# Zoetrope.net
KiCad netlist of a schematic drawn in EAGLE
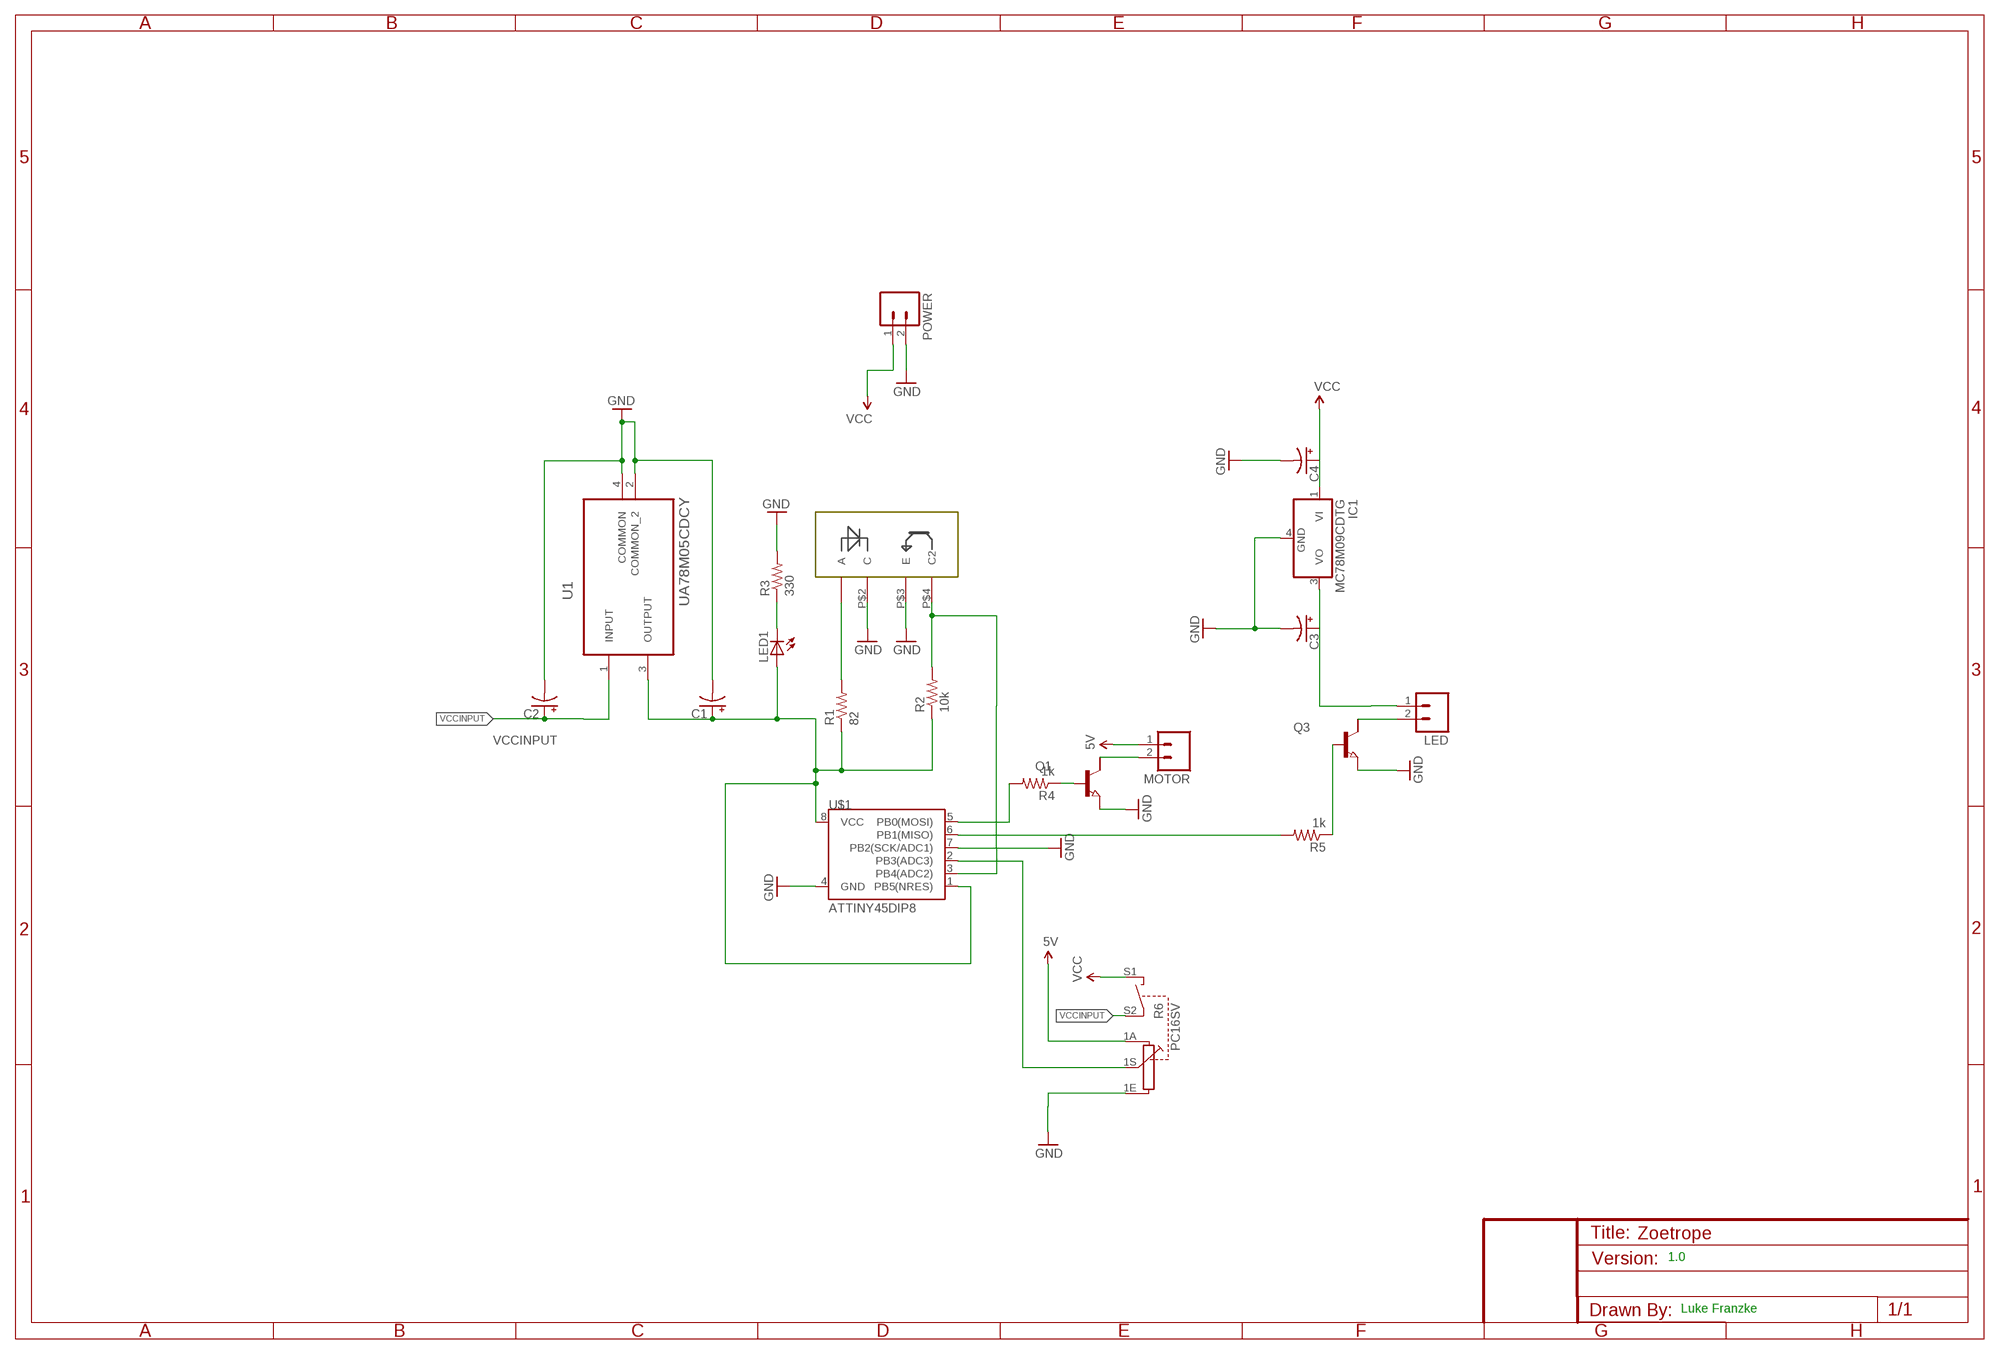
[diagram p0: schematic, sheet 1]

(export (version "E")
  (design (tool "Eeschema 10.0.6"))
  (components
    (comp (ref "C1")
      (value "CAP_POL1206")
      (footprint "eagle-import:EIA3216")
      (libsource (lib "eagle-import") (part "CAP_POL1206"))
    )
    (comp (ref "C2")
      (value "CAP_POL1206")
      (footprint "eagle-import:EIA3216")
      (libsource (lib "eagle-import") (part "CAP_POL1206"))
    )
    (comp (ref "C3")
      (value "CAP_POL1206")
      (footprint "eagle-import:EIA3216")
      (libsource (lib "eagle-import") (part "CAP_POL1206"))
    )
    (comp (ref "C4")
      (value "CAP_POL1206")
      (footprint "eagle-import:EIA3216")
      (libsource (lib "eagle-import") (part "CAP_POL1206"))
    )
    (comp (ref "IC1")
      (value "MC78M09CDTG")
      (footprint "eagle-import:DPACK_3")
      (libsource (lib "eagle-import") (part "MC78M09CDTG"))
    )
    (comp (ref "LED")
      (value "M02")
      (footprint "eagle-import:02P")
      (libsource (lib "eagle-import") (part "M02"))
    )
    (comp (ref "LED1")
      (value "LED1206")
      (footprint "eagle-import:LED-1206")
      (libsource (lib "eagle-import") (part "LED1206"))
    )
    (comp (ref "MOTOR")
      (value "M02")
      (footprint "eagle-import:02P")
      (libsource (lib "eagle-import") (part "M02"))
    )
    (comp (ref "POWER")
      (value "M02")
      (footprint "eagle-import:02P")
      (libsource (lib "eagle-import") (part "M02"))
    )
    (comp (ref "Q1")
      (value "NPN-TRANSISTIOR-2COLSOT89")
      (footprint "eagle-import:SOT89")
      (libsource (lib "eagle-import") (part "NPN-TRANSISTIOR-2COLSOT89"))
    )
    (comp (ref "Q3")
      (value "NPN-TRANSISTIOR-2COLSOT89")
      (footprint "eagle-import:SOT89")
      (libsource (lib "eagle-import") (part "NPN-TRANSISTIOR-2COLSOT89"))
    )
    (comp (ref "R1")
      (value "82")
      (footprint "eagle-import:1206")
      (libsource (lib "eagle-import") (part "RESISTOR1206"))
    )
    (comp (ref "R2")
      (value "10k")
      (footprint "eagle-import:1206")
      (libsource (lib "eagle-import") (part "RESISTOR1206"))
    )
    (comp (ref "R3")
      (value "330")
      (footprint "eagle-import:1206")
      (libsource (lib "eagle-import") (part "RESISTOR1206"))
    )
    (comp (ref "R4")
      (value "1k")
      (footprint "eagle-import:1206")
      (libsource (lib "eagle-import") (part "RESISTOR1206"))
    )
    (comp (ref "R5")
      (value "1k")
      (footprint "eagle-import:1206")
      (libsource (lib "eagle-import") (part "RESISTOR1206"))
    )
    (comp (ref "R6")
      (value "PC16SV")
      (footprint "eagle-import:PC16SV")
      (libsource (lib "eagle-import") (part "PC16SV"))
    )
    (comp (ref "U$1")
      (value "ATTINY45DIP8")
      (footprint "eagle-import:DIP08")
      (libsource (lib "eagle-import") (part "ATTINY45DIP8"))
    )
    (comp (ref "U$2")
      (value "TCRT1000")
      (footprint "eagle-import:TCRT1000")
      (libsource (lib "eagle-import") (part "TCRT1000"))
    )
    (comp (ref "U1")
      (value "UA78M05CDCY")
      (footprint "eagle-import:SOT230P700X180-4N")
      (libsource (lib "eagle-import") (part "UA78M05CDCY"))
    )
  )
  (nets
    (net (code "1") (name "5V") (class "Default")
      (node (ref "C1") (pin "A") (pinfunction "+_A") (pintype "passive"))
      (node (ref "LED1") (pin "A") (pinfunction "A_A") (pintype "passive"))
      (node (ref "MOTOR") (pin "1") (pinfunction "1_1") (pintype "passive"))
      (node (ref "R1") (pin "1") (pinfunction "1_1") (pintype "passive"))
      (node (ref "R2") (pin "1") (pinfunction "1_1") (pintype "passive"))
      (node (ref "R6") (pin "1A") (pinfunction "1A_1A") (pintype "passive"))
      (node (ref "U$1") (pin "1") (pinfunction "PB5(NRES)_1") (pintype "bidirectional"))
      (node (ref "U$1") (pin "8") (pinfunction "VCC_8") (pintype "bidirectional"))
      (node (ref "U1") (pin "3") (pinfunction "OUTPUT_3") (pintype "input"))
    )
    (net (code "2") (name "GND") (class "Default")
      (node (ref "C1") (pin "C") (pinfunction "-_C") (pintype "passive"))
      (node (ref "C2") (pin "C") (pinfunction "-_C") (pintype "passive"))
      (node (ref "C3") (pin "C") (pinfunction "-_C") (pintype "passive"))
      (node (ref "C4") (pin "C") (pinfunction "-_C") (pintype "passive"))
      (node (ref "IC1") (pin "4") (pinfunction "GND_4") (pintype "passive"))
      (node (ref "POWER") (pin "2") (pinfunction "2_2") (pintype "passive"))
      (node (ref "Q1") (pin "3") (pinfunction "E_3") (pintype "passive"))
      (node (ref "Q3") (pin "3") (pinfunction "E_3") (pintype "passive"))
      (node (ref "R3") (pin "2") (pinfunction "2_2") (pintype "passive"))
      (node (ref "R6") (pin "1E") (pinfunction "1E_1E") (pintype "passive"))
      (node (ref "U$1") (pin "4") (pinfunction "GND_4") (pintype "bidirectional"))
      (node (ref "U$1") (pin "7") (pinfunction "PB2(SCK/ADC1)_7") (pintype "bidirectional"))
      (node (ref "U$2") (pin "P$2") (pinfunction "C_P$2") (pintype "output"))
      (node (ref "U$2") (pin "P$3") (pinfunction "E_P$3") (pintype "bidirectional"))
      (node (ref "U1") (pin "2") (pinfunction "COMMON_2_2") (pintype "output"))
      (node (ref "U1") (pin "4") (pinfunction "COMMON_4") (pintype "output"))
    )
    (net (code "3") (name "Net-(C3-+)") (class "Default")
      (node (ref "C3") (pin "A") (pinfunction "+_A") (pintype "passive"))
      (node (ref "IC1") (pin "3") (pinfunction "VO_3") (pintype "passive"))
      (node (ref "LED") (pin "1") (pinfunction "1_1") (pintype "passive"))
    )
    (net (code "4") (name "Net-(LED1-PadC)") (class "Default")
      (node (ref "LED1") (pin "C") (pinfunction "C_C") (pintype "passive"))
      (node (ref "R3") (pin "1") (pinfunction "1_1") (pintype "passive"))
    )
    (net (code "5") (name "Net-(Q1-B)") (class "Default")
      (node (ref "Q1") (pin "1") (pinfunction "B_1") (pintype "passive"))
      (node (ref "R4") (pin "1") (pinfunction "1_1") (pintype "passive"))
    )
    (net (code "6") (name "Net-(Q1-C)") (class "Default")
      (node (ref "MOTOR") (pin "2") (pinfunction "2_2") (pintype "passive"))
      (node (ref "Q1") (pin "2") (pinfunction "C_2") (pintype "passive"))
    )
    (net (code "7") (name "Net-(Q3-B)") (class "Default")
      (node (ref "Q3") (pin "1") (pinfunction "B_1") (pintype "passive"))
      (node (ref "R5") (pin "1") (pinfunction "1_1") (pintype "passive"))
    )
    (net (code "8") (name "Net-(Q3-C)") (class "Default")
      (node (ref "LED") (pin "2") (pinfunction "2_2") (pintype "passive"))
      (node (ref "Q3") (pin "2") (pinfunction "C_2") (pintype "passive"))
    )
    (net (code "9") (name "Net-(U$1-PB0(MOSI))") (class "Default")
      (node (ref "R4") (pin "2") (pinfunction "2_2") (pintype "passive"))
      (node (ref "U$1") (pin "5") (pinfunction "PB0(MOSI)_5") (pintype "bidirectional"))
    )
    (net (code "10") (name "Net-(U$1-PB1(MISO))") (class "Default")
      (node (ref "R5") (pin "2") (pinfunction "2_2") (pintype "passive"))
      (node (ref "U$1") (pin "6") (pinfunction "PB1(MISO)_6") (pintype "bidirectional"))
    )
    (net (code "11") (name "Net-(U$1-PB3(ADC3))") (class "Default")
      (node (ref "R6") (pin "1S") (pinfunction "1S_1S") (pintype "passive"))
      (node (ref "U$1") (pin "2") (pinfunction "PB3(ADC3)_2") (pintype "bidirectional"))
    )
    (net (code "12") (name "Net-(U$1-PB4(ADC2))") (class "Default")
      (node (ref "R2") (pin "2") (pinfunction "2_2") (pintype "passive"))
      (node (ref "U$1") (pin "3") (pinfunction "PB4(ADC2)_3") (pintype "bidirectional"))
      (node (ref "U$2") (pin "P$4") (pinfunction "C2_P$4") (pintype "output"))
    )
    (net (code "13") (name "Net-(U$2-A)") (class "Default")
      (node (ref "R1") (pin "2") (pinfunction "2_2") (pintype "passive"))
      (node (ref "U$2") (pin "P$1") (pinfunction "A_P$1") (pintype "bidirectional"))
    )
    (net (code "14") (name "VCC") (class "Default")
      (node (ref "C4") (pin "A") (pinfunction "+_A") (pintype "passive"))
      (node (ref "IC1") (pin "1") (pinfunction "VI_1") (pintype "input"))
      (node (ref "POWER") (pin "1") (pinfunction "1_1") (pintype "passive"))
      (node (ref "R6") (pin "S1") (pinfunction "S1_S1") (pintype "passive"))
    )
    (net (code "15") (name "VCCINPUT") (class "Default")
      (node (ref "C2") (pin "A") (pinfunction "+_A") (pintype "passive"))
      (node (ref "R6") (pin "S2") (pinfunction "S2_S2") (pintype "passive"))
      (node (ref "U1") (pin "1") (pinfunction "INPUT_1") (pintype "input"))
    )
    (net (code "16") (name "unconnected-(Q1-C{slash}-Pad2@1)") (class "Default")
      (node (ref "Q1") (pin "2@1") (pinfunction "C/_2@1") (pintype "passive"))
    )
    (net (code "17") (name "unconnected-(Q3-C{slash}-Pad2@1)") (class "Default")
      (node (ref "Q3") (pin "2@1") (pinfunction "C/_2@1") (pintype "passive"))
    )
  )
)
